# power.net
KiCad netlist of a schematic drawn in Altium Designer
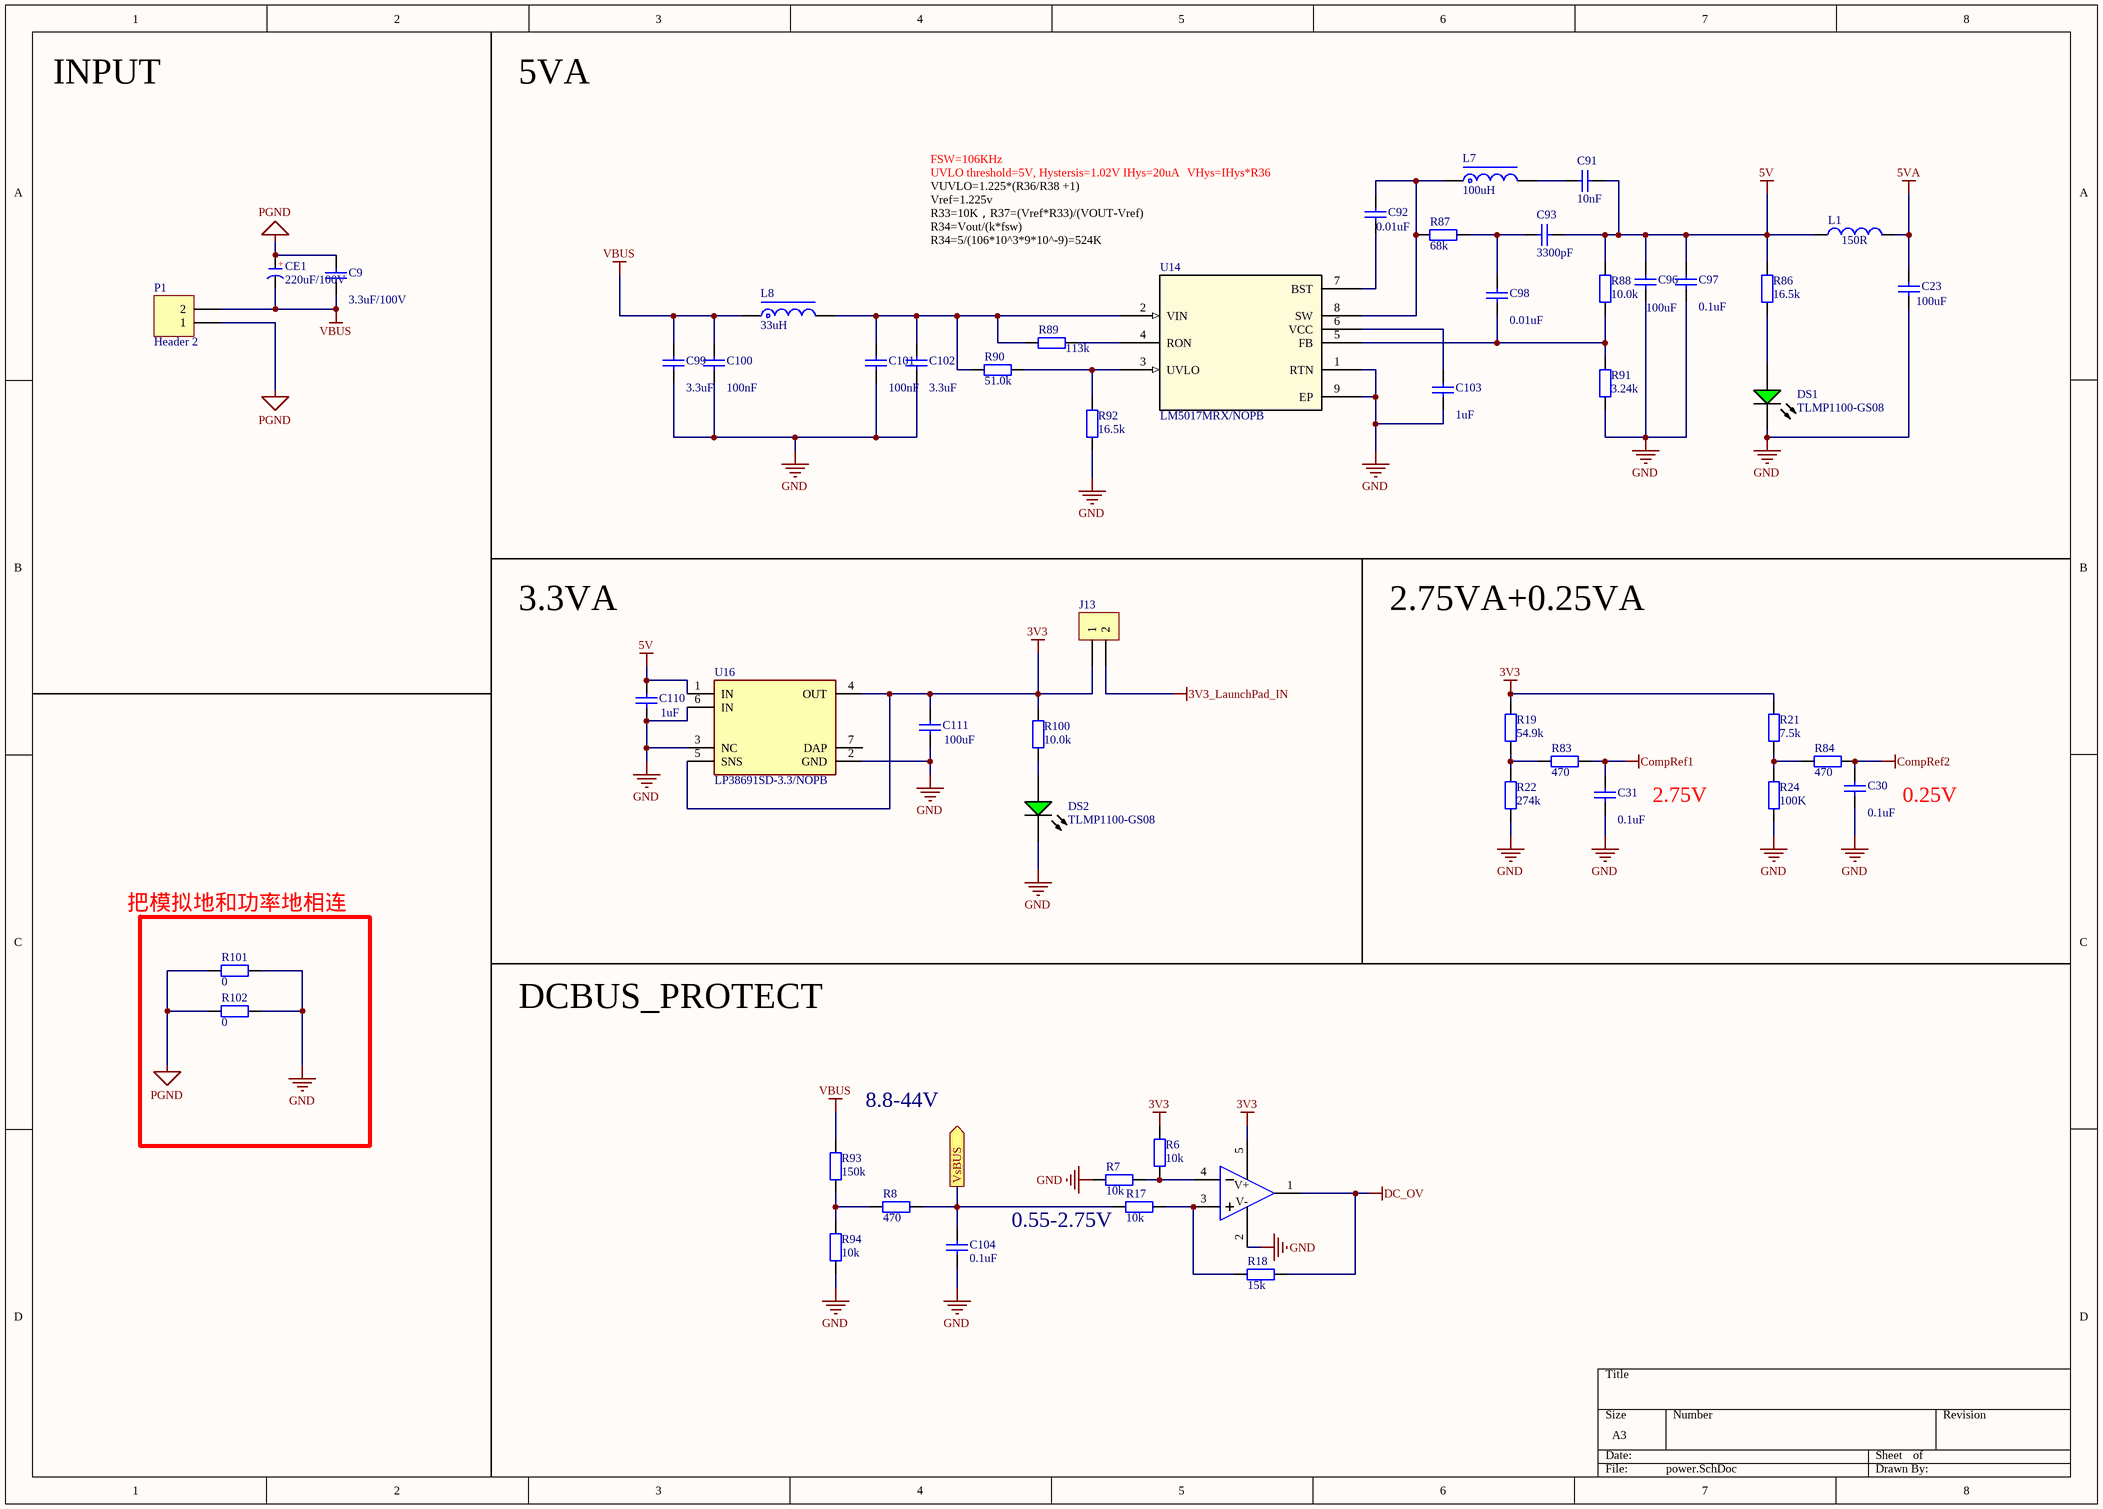
[diagram p0: power.SchDoc]

(export (version "E")
  (design (tool "Eeschema 10.0.6"))
  (components
    (comp (ref "C9")
      (value "3.3uF/100V")
      (footprint "CAPC1608X06N")
      (description "Capacitor")
      (fields (field (name "PUBLISHER") "Altium Limited"))
      (libsource (lib "Simscale") (part "Cap"))
    )
    (comp (ref "C23")
      (value "100uF")
      (footprint "CAPC1608X06N")
      (description "Capacitor")
      (fields (field (name "PUBLISHER") "Altium Limited"))
      (libsource (lib "Simscale") (part "Cap"))
    )
    (comp (ref "C30")
      (value "0.1uF")
      (footprint "CAPC1608X06N")
      (description "Capacitor")
      (fields (field (name "PUBLISHER") "Altium Limited"))
      (libsource (lib "Simscale") (part "Cap"))
    )
    (comp (ref "C31")
      (value "0.1uF")
      (footprint "CAPC1608X06N")
      (description "Capacitor")
      (fields (field (name "PUBLISHER") "Altium Limited"))
      (libsource (lib "Simscale") (part "Cap"))
    )
    (comp (ref "C91")
      (value "10nF")
      (footprint "CAPC1608X06N")
      (description "Capacitor")
      (fields (field (name "PUBLISHER") "Altium Limited"))
      (libsource (lib "Simscale") (part "Cap"))
    )
    (comp (ref "C92")
      (value "0.01uF")
      (footprint "CAPC1608X06N")
      (description "Capacitor")
      (fields (field (name "PUBLISHER") "Altium Limited"))
      (libsource (lib "Simscale") (part "Cap"))
    )
    (comp (ref "C93")
      (value "3300pF")
      (footprint "CAPC1608X06N")
      (description "Capacitor")
      (fields (field (name "PUBLISHER") "Altium Limited"))
      (libsource (lib "Simscale") (part "Cap"))
    )
    (comp (ref "C96")
      (value "100uF")
      (footprint "CAPC1608X06N")
      (description "Capacitor")
      (fields (field (name "PUBLISHER") "Altium Limited"))
      (libsource (lib "Simscale") (part "Cap"))
    )
    (comp (ref "C97")
      (value "0.1uF")
      (footprint "CAPC1608X06N")
      (description "Capacitor")
      (fields (field (name "PUBLISHER") "Altium Limited"))
      (libsource (lib "Simscale") (part "Cap"))
    )
    (comp (ref "C98")
      (value "0.01uF")
      (footprint "CAPC1608X06N")
      (description "Capacitor")
      (fields (field (name "PUBLISHER") "Altium Limited"))
      (libsource (lib "Simscale") (part "Cap"))
    )
    (comp (ref "C99")
      (value "3.3uF")
      (footprint "CAPC1608X06N")
      (description "Capacitor")
      (fields (field (name "PUBLISHER") "Altium Limited"))
      (libsource (lib "Soardra") (part "Cap"))
    )
    (comp (ref "C100")
      (value "100nF")
      (footprint "CAPC1608X06N")
      (description "Capacitor")
      (fields (field (name "PUBLISHER") "Altium Limited"))
      (libsource (lib "Soardra") (part "Cap"))
    )
    (comp (ref "C101")
      (value "100nF")
      (footprint "CAPC1608X06N")
      (description "Capacitor")
      (fields (field (name "PUBLISHER") "Altium Limited"))
      (libsource (lib "Simscale") (part "Cap"))
    )
    (comp (ref "C102")
      (value "3.3uF")
      (footprint "CAPC1608X06N")
      (description "Capacitor")
      (fields (field (name "PUBLISHER") "Altium Limited"))
      (libsource (lib "Simscale") (part "Cap"))
    )
    (comp (ref "C103")
      (value "1uF")
      (footprint "CAPC1608X06N")
      (description "Capacitor")
      (fields (field (name "PUBLISHER") "Altium Limited"))
      (libsource (lib "Simscale") (part "Cap"))
    )
    (comp (ref "C104")
      (value "0.1uF")
      (footprint "CAPC1608X06N")
      (description "Capacitor")
      (fields (field (name "PUBLISHER") "Altium Limited"))
      (libsource (lib "Simscale") (part "Cap"))
    )
    (comp (ref "C110")
      (value "1uF")
      (footprint "CAPC1608X06N")
      (description "Capacitor")
      (fields (field (name "PUBLISHER") "Altium Limited"))
      (libsource (lib "Simscale") (part "Cap"))
    )
    (comp (ref "C111")
      (value "100uF")
      (footprint "CAPC1608X06N")
      (description "Capacitor")
      (fields (field (name "PUBLISHER") "Altium Limited"))
      (libsource (lib "Simscale") (part "Cap"))
    )
    (comp (ref "CE1")
      (value "220uF/100V")
      (footprint "CAP 5.0*12.5*20")
      (description "直插电解电容")
      (libsource (lib "0.1 - 电阻-电容-电感") (part "CE"))
    )
    (comp (ref "DS1")
      (value "TLMP1100-GS08")
      (footprint "VISH-TLMX1100_V")
      (description "LED, RED, 2.1 V, -40 to 100 degC, 2-Pin SMD (0603), RoHS, Tape and Reel")
      (fields (field (name "TOLERANCE") "5%"))
      (libsource (lib "Simscale") (part "CMP-1666-00027-1_1"))
    )
    (comp (ref "DS2")
      (value "TLMP1100-GS08")
      (footprint "VISH-TLMX1100_V")
      (description "LED, RED, 2.1 V, -40 to 100 degC, 2-Pin SMD (0603), RoHS, Tape and Reel")
      (fields (field (name "TOLERANCE") "5%"))
      (libsource (lib "Simscale") (part "CMP-1666-00027-1_1"))
    )
    (comp (ref "J13") (value "CON2") (footprint "DG1282-5.0") (libsource (lib "常用元件库") (part "CON2")))
    (comp (ref "L1")
      (value "150R")
      (footprint "IND-SMD_L5.5-W5.2")
      (description "Inductor")
      (fields (field (name "PUBLISHER") "Altium Limited"))
      (libsource (lib "Miscellaneous Devices") (part "Inductor"))
    )
    (comp (ref "L7")
      (value "100uH")
      (footprint "NR4018")
      (description "NR磁胶电感")
      (fields (field (name "版权归属") "来自淘宝 ID：黄晶宝石"))
      (libsource (lib "0.1 - 电阻-电容-电感") (part "L-NR"))
    )
    (comp (ref "L8")
      (value "33uH")
      (footprint "NR2520")
      (description "NR磁胶电感")
      (fields (field (name "版权归属") "来自淘宝 ID：黄晶宝石"))
      (libsource (lib "0.1 - 电阻-电容-电感") (part "L-NR"))
    )
    (comp (ref "P1")
      (value "Header 2")
      (footprint "HDR1X2")
      (description "Header, 2-Pin")
      (fields (field (name "PUBLISHER") "Altium Limited"))
      (libsource (lib "Simscale") (part "Header 2"))
    )
    (comp (ref "R6")
      (value "10k")
      (footprint "RESC1608X05N")
      (description "贴片电阻")
      (libsource (lib "") (part "0603 100KΩ (1003) 1%_4_3"))
    )
    (comp (ref "R7")
      (value "10k")
      (footprint "RESC1608X05N")
      (description "贴片电阻")
      (libsource (lib "") (part "0603 100KΩ (1003) 1%_4_2"))
    )
    (comp (ref "R8")
      (value "470")
      (footprint "RESC1608X05N")
      (description "贴片电阻")
      (libsource (lib "") (part "0603 100KΩ (1003) 1%_4_2"))
    )
    (comp (ref "R17")
      (value "10k")
      (footprint "RESC1608X05N")
      (description "贴片电阻")
      (libsource (lib "") (part "0603 100KΩ (1003) 1%_4_2"))
    )
    (comp (ref "R18")
      (value "15k")
      (footprint "RESC1608X05N")
      (description "贴片电阻")
      (libsource (lib "") (part "0603 100KΩ (1003) 1%_4_2"))
    )
    (comp (ref "R19")
      (value "54.9k")
      (footprint "RESC1608X05N")
      (description "贴片电阻")
      (libsource (lib "Simscale") (part "0603 100KΩ (1003) 1%_4"))
    )
    (comp (ref "R21")
      (value "7.5k")
      (footprint "RESC1608X05N")
      (description "贴片电阻")
      (libsource (lib "Simscale") (part "0603 100KΩ (1003) 1%_4"))
    )
    (comp (ref "R22")
      (value "274k")
      (footprint "RESC1608X05N")
      (description "贴片电阻")
      (libsource (lib "Simscale") (part "0603 100KΩ (1003) 1%_4"))
    )
    (comp (ref "R24")
      (value "100K")
      (footprint "RESC1608X05N")
      (description "贴片电阻")
      (libsource (lib "Simscale") (part "0603 100KΩ (1003) 1%_4"))
    )
    (comp (ref "R83")
      (value "470")
      (footprint "RESC1608X05N")
      (description "贴片电阻")
      (libsource (lib "") (part "0603 100KΩ (1003) 1%_4_2"))
    )
    (comp (ref "R84")
      (value "470")
      (footprint "RESC1608X05N")
      (description "贴片电阻")
      (libsource (lib "") (part "0603 100KΩ (1003) 1%_4_2"))
    )
    (comp (ref "R86")
      (value "16.5k")
      (footprint "RESC1608X05N")
      (description "贴片电阻")
      (libsource (lib "Simscale") (part "0603 100KΩ (1003) 1%_4"))
    )
    (comp (ref "R87")
      (value "68k")
      (footprint "RESC1608X05N")
      (description "贴片电阻")
      (libsource (lib "") (part "0603 100KΩ (1003) 1%_4_2"))
    )
    (comp (ref "R88")
      (value "10.0k")
      (footprint "RESC1608X05N")
      (description "贴片电阻")
      (libsource (lib "Simscale") (part "0603 100KΩ (1003) 1%_4"))
    )
    (comp (ref "R89")
      (value "113k")
      (footprint "RESC1608X05N")
      (description "贴片电阻")
      (libsource (lib "") (part "0603 100KΩ (1003) 1%_4_1"))
    )
    (comp (ref "R90")
      (value "51.0k")
      (footprint "RESC1608X05N")
      (description "贴片电阻")
      (libsource (lib "") (part "0603 100KΩ (1003) 1%_4_1"))
    )
    (comp (ref "R91")
      (value "3.24k")
      (footprint "RESC1608X05N")
      (description "贴片电阻")
      (libsource (lib "Simscale") (part "0603 100KΩ (1003) 1%_4"))
    )
    (comp (ref "R92")
      (value "16.5k")
      (footprint "RESC1608X05N")
      (description "贴片电阻")
      (libsource (lib "Simscale") (part "0603 100KΩ (1003) 1%_4"))
    )
    (comp (ref "R93")
      (value "150k")
      (footprint "RESC1608X05N")
      (description "贴片电阻")
      (libsource (lib "Simscale") (part "0603 100KΩ (1003) 1%_4"))
    )
    (comp (ref "R94")
      (value "10k")
      (footprint "RESC1608X05N")
      (description "贴片电阻")
      (libsource (lib "Simscale") (part "0603 100KΩ (1003) 1%_4"))
    )
    (comp (ref "R100")
      (value "10.0k")
      (footprint "RESC1608X05N")
      (description "贴片电阻")
      (libsource (lib "Simscale") (part "0603 100KΩ (1003) 1%_4"))
    )
    (comp (ref "R101")
      (value "0")
      (footprint "RESC1608X05N")
      (description "贴片电阻")
      (libsource (lib "") (part "0603 100KΩ (1003) 1%_4_2"))
    )
    (comp (ref "R102")
      (value "0")
      (footprint "RESC1608X05N")
      (description "贴片电阻")
      (libsource (lib "") (part "0603 100KΩ (1003) 1%_4_2"))
    )
    (comp (ref "U6")
      (value "TLV3201AIDBVR")
      (footprint "SOT-23-5_L3.0-W1.7-P0.95-LS2.8-BR")
      (fields (field (name "MANUFACTURER") "TI(德州仪器)"))
      (libsource (lib "TLV3201AIDBVR1_TLV3201AIDBVR.schdoc") (part "TLV3201AIDBVR"))
    )
    (comp (ref "U14")
      (value "LM5017MRX/NOPB")
      (footprint "DDA8_3P1X2P41")
      (description "No Description Available")
      (fields (field (name "COPYRIGHT") "Copyright (C) 2024 Ultra Librarian. All rights reserved."))
      (libsource (lib "LM5017MRXNOPB") (part "LM5017MRXNOPB"))
    )
    (comp (ref "U16")
      (value "LP38691SD-3.3/NOPB")
      (footprint "FP-NGG0006A-MFG")
      (description "IC REG LINEAR 3.3V 500MA 6WSON")
      (libsource (lib "Altium Content Vault") (part "560842684473682ac15f67370b5a5a6"))
    )
  )
  (nets
    (net (code "1") (name "/VsBUS") (class "Default")
      (node (ref "C104") (pin "1") (pinfunction "1_1") (pintype "passive"))
      (node (ref "R17") (pin "2") (pinfunction "2_2") (pintype "passive"))
      (node (ref "R8") (pin "1") (pinfunction "1_1") (pintype "passive"))
    )
    (net (code "2") (name "3V3") (class "Default")
      (node (ref "C111") (pin "2") (pinfunction "2_2") (pintype "passive"))
      (node (ref "J13") (pin "1") (pinfunction "1_1") (pintype "passive"))
      (node (ref "R100") (pin "2") (pinfunction "2_2") (pintype "passive"))
      (node (ref "R19") (pin "2") (pinfunction "2_2") (pintype "passive"))
      (node (ref "R21") (pin "2") (pinfunction "2_2") (pintype "passive"))
      (node (ref "R6") (pin "1") (pinfunction "1_1") (pintype "passive"))
      (node (ref "U16") (pin "4") (pinfunction "OUT_4") (pintype "power_in"))
      (node (ref "U16") (pin "5") (pinfunction "SNS_5") (pintype "power_in"))
      (node (ref "U6") (pin "5") (pinfunction "VCC_5") (pintype "passive"))
    )
    (net (code "3") (name "3V3_LaunchPad_IN") (class "Default")
      (node (ref "J13") (pin "2") (pinfunction "2_2") (pintype "passive"))
    )
    (net (code "4") (name "5V") (class "Default")
      (node (ref "C110") (pin "2") (pinfunction "2_2") (pintype "passive"))
      (node (ref "C91") (pin "2") (pinfunction "2_2") (pintype "passive"))
      (node (ref "C93") (pin "1") (pinfunction "1_1") (pintype "passive"))
      (node (ref "C96") (pin "2") (pinfunction "2_2") (pintype "passive"))
      (node (ref "C97") (pin "2") (pinfunction "2_2") (pintype "passive"))
      (node (ref "L1") (pin "1") (pinfunction "1_1") (pintype "passive"))
      (node (ref "R86") (pin "2") (pinfunction "2_2") (pintype "passive"))
      (node (ref "R88") (pin "2") (pinfunction "2_2") (pintype "passive"))
      (node (ref "U16") (pin "1") (pinfunction "IN_1") (pintype "power_in"))
    )
    (net (code "5") (name "5VA") (class "Default")
      (node (ref "C23") (pin "2") (pinfunction "2_2") (pintype "passive"))
      (node (ref "L1") (pin "2") (pinfunction "2_2") (pintype "passive"))
    )
    (net (code "6") (name "CompRef1") (class "Default")
      (node (ref "C31") (pin "2") (pinfunction "2_2") (pintype "passive"))
      (node (ref "R83") (pin "1") (pinfunction "1_1") (pintype "passive"))
    )
    (net (code "7") (name "CompRef2") (class "Default")
      (node (ref "C30") (pin "2") (pinfunction "2_2") (pintype "passive"))
      (node (ref "R84") (pin "1") (pinfunction "1_1") (pintype "passive"))
    )
    (net (code "8") (name "DC_OV") (class "Default")
      (node (ref "R18") (pin "1") (pinfunction "1_1") (pintype "passive"))
      (node (ref "U6") (pin "1") (pinfunction "OUT_1") (pintype "passive"))
    )
    (net (code "9") (name "GND") (class "Default")
      (node (ref "C100") (pin "2") (pinfunction "2_2") (pintype "passive"))
      (node (ref "C101") (pin "2") (pinfunction "2_2") (pintype "passive"))
      (node (ref "C102") (pin "1") (pinfunction "1_1") (pintype "passive"))
      (node (ref "C103") (pin "1") (pinfunction "1_1") (pintype "passive"))
      (node (ref "C104") (pin "2") (pinfunction "2_2") (pintype "passive"))
      (node (ref "C110") (pin "1") (pinfunction "1_1") (pintype "passive"))
      (node (ref "C111") (pin "1") (pinfunction "1_1") (pintype "passive"))
      (node (ref "C23") (pin "1") (pinfunction "1_1") (pintype "passive"))
      (node (ref "C30") (pin "1") (pinfunction "1_1") (pintype "passive"))
      (node (ref "C31") (pin "1") (pinfunction "1_1") (pintype "passive"))
      (node (ref "C96") (pin "1") (pinfunction "1_1") (pintype "passive"))
      (node (ref "C97") (pin "1") (pinfunction "1_1") (pintype "passive"))
      (node (ref "C99") (pin "2") (pinfunction "2_2") (pintype "passive"))
      (node (ref "DS1") (pin "2") (pinfunction "K_2") (pintype "passive"))
      (node (ref "DS2") (pin "2") (pinfunction "K_2") (pintype "passive"))
      (node (ref "R101") (pin "1") (pinfunction "1_1") (pintype "passive"))
      (node (ref "R102") (pin "1") (pinfunction "1_1") (pintype "passive"))
      (node (ref "R22") (pin "1") (pinfunction "1_1") (pintype "passive"))
      (node (ref "R24") (pin "1") (pinfunction "1_1") (pintype "passive"))
      (node (ref "R7") (pin "2") (pinfunction "2_2") (pintype "passive"))
      (node (ref "R91") (pin "1") (pinfunction "1_1") (pintype "passive"))
      (node (ref "R92") (pin "1") (pinfunction "1_1") (pintype "passive"))
      (node (ref "R94") (pin "1") (pinfunction "1_1") (pintype "passive"))
      (node (ref "U14") (pin "1") (pinfunction "RTN_1") (pintype "power_in"))
      (node (ref "U14") (pin "9") (pinfunction "EP_9") (pintype "passive"))
      (node (ref "U16") (pin "2") (pinfunction "GND_2") (pintype "power_in"))
      (node (ref "U16") (pin "3") (pinfunction "NC_3") (pintype "passive"))
      (node (ref "U16") (pin "6") (pinfunction "IN_6") (pintype "power_in"))
      (node (ref "U6") (pin "2") (pinfunction "GND_2") (pintype "passive"))
    )
    (net (code "10") (name "Net-(C91-Pad1)") (class "Default")
      (node (ref "C91") (pin "1") (pinfunction "1_1") (pintype "passive"))
      (node (ref "L7") (pin "2") (pinfunction "2_2") (pintype "passive"))
    )
    (net (code "11") (name "Net-(C93-Pad2)") (class "Default")
      (node (ref "C93") (pin "2") (pinfunction "2_2") (pintype "passive"))
      (node (ref "C98") (pin "2") (pinfunction "2_2") (pintype "passive"))
      (node (ref "R87") (pin "1") (pinfunction "1_1") (pintype "passive"))
    )
    (net (code "12") (name "Net-(DS1-A)") (class "Default")
      (node (ref "DS1") (pin "1") (pinfunction "A_1") (pintype "passive"))
      (node (ref "R86") (pin "1") (pinfunction "1_1") (pintype "passive"))
    )
    (net (code "13") (name "Net-(DS2-A)") (class "Default")
      (node (ref "DS2") (pin "1") (pinfunction "A_1") (pintype "passive"))
      (node (ref "R100") (pin "1") (pinfunction "1_1") (pintype "passive"))
    )
    (net (code "14") (name "Net-(R8-Pad2)") (class "Default")
      (node (ref "R8") (pin "2") (pinfunction "2_2") (pintype "passive"))
      (node (ref "R93") (pin "1") (pinfunction "1_1") (pintype "passive"))
      (node (ref "R94") (pin "2") (pinfunction "2_2") (pintype "passive"))
    )
    (net (code "15") (name "Net-(R19-Pad1)") (class "Default")
      (node (ref "R19") (pin "1") (pinfunction "1_1") (pintype "passive"))
      (node (ref "R22") (pin "2") (pinfunction "2_2") (pintype "passive"))
      (node (ref "R83") (pin "2") (pinfunction "2_2") (pintype "passive"))
    )
    (net (code "16") (name "Net-(R21-Pad1)") (class "Default")
      (node (ref "R21") (pin "1") (pinfunction "1_1") (pintype "passive"))
      (node (ref "R24") (pin "2") (pinfunction "2_2") (pintype "passive"))
      (node (ref "R84") (pin "2") (pinfunction "2_2") (pintype "passive"))
    )
    (net (code "17") (name "Net-(U6-IN+)") (class "Default")
      (node (ref "R17") (pin "1") (pinfunction "1_1") (pintype "passive"))
      (node (ref "R18") (pin "2") (pinfunction "2_2") (pintype "passive"))
      (node (ref "U6") (pin "3") (pinfunction "IN+_3") (pintype "passive"))
    )
    (net (code "18") (name "Net-(U6-IN-)") (class "Default")
      (node (ref "R6") (pin "2") (pinfunction "2_2") (pintype "passive"))
      (node (ref "R7") (pin "1") (pinfunction "1_1") (pintype "passive"))
      (node (ref "U6") (pin "4") (pinfunction "IN-_4") (pintype "passive"))
    )
    (net (code "19") (name "Net-(U14-BST)") (class "Default")
      (node (ref "C92") (pin "1") (pinfunction "1_1") (pintype "passive"))
      (node (ref "U14") (pin "7") (pinfunction "BST_7") (pintype "passive"))
    )
    (net (code "20") (name "Net-(U14-FB)") (class "Default")
      (node (ref "C98") (pin "1") (pinfunction "1_1") (pintype "passive"))
      (node (ref "R88") (pin "1") (pinfunction "1_1") (pintype "passive"))
      (node (ref "R91") (pin "2") (pinfunction "2_2") (pintype "passive"))
      (node (ref "U14") (pin "5") (pinfunction "FB_5") (pintype "passive"))
    )
    (net (code "21") (name "Net-(U14-RON)") (class "Default")
      (node (ref "R89") (pin "2") (pinfunction "2_2") (pintype "passive"))
      (node (ref "U14") (pin "4") (pinfunction "RON_4") (pintype "passive"))
    )
    (net (code "22") (name "Net-(U14-SW)") (class "Default")
      (node (ref "C92") (pin "2") (pinfunction "2_2") (pintype "passive"))
      (node (ref "L7") (pin "1") (pinfunction "1_1") (pintype "passive"))
      (node (ref "R87") (pin "2") (pinfunction "2_2") (pintype "passive"))
      (node (ref "U14") (pin "8") (pinfunction "SW_8") (pintype "passive"))
    )
    (net (code "23") (name "Net-(U14-UVLO)") (class "Default")
      (node (ref "R90") (pin "2") (pinfunction "2_2") (pintype "passive"))
      (node (ref "R92") (pin "2") (pinfunction "2_2") (pintype "passive"))
      (node (ref "U14") (pin "3") (pinfunction "UVLO_3") (pintype "input"))
    )
    (net (code "24") (name "Net-(U14-VCC)") (class "Default")
      (node (ref "C103") (pin "2") (pinfunction "2_2") (pintype "passive"))
      (node (ref "U14") (pin "6") (pinfunction "VCC_6") (pintype "power_in"))
    )
    (net (code "25") (name "Net-(U14-VIN)") (class "Default")
      (node (ref "C101") (pin "1") (pinfunction "1_1") (pintype "passive"))
      (node (ref "C102") (pin "2") (pinfunction "2_2") (pintype "passive"))
      (node (ref "L8") (pin "2") (pinfunction "2_2") (pintype "passive"))
      (node (ref "R89") (pin "1") (pinfunction "1_1") (pintype "passive"))
      (node (ref "R90") (pin "1") (pinfunction "1_1") (pintype "passive"))
      (node (ref "U14") (pin "2") (pinfunction "VIN_2") (pintype "input"))
    )
    (net (code "26") (name "PGND") (class "Default")
      (node (ref "C9") (pin "2") (pinfunction "2_2") (pintype "passive"))
      (node (ref "CE1") (pin "1") (pinfunction "A_1") (pintype "passive"))
      (node (ref "P1") (pin "1") (pinfunction "1_1") (pintype "passive"))
      (node (ref "R101") (pin "2") (pinfunction "2_2") (pintype "passive"))
      (node (ref "R102") (pin "2") (pinfunction "2_2") (pintype "passive"))
    )
    (net (code "27") (name "VBUS") (class "Default")
      (node (ref "C100") (pin "1") (pinfunction "1_1") (pintype "passive"))
      (node (ref "C9") (pin "1") (pinfunction "1_1") (pintype "passive"))
      (node (ref "C99") (pin "1") (pinfunction "1_1") (pintype "passive"))
      (node (ref "CE1") (pin "2") (pinfunction "K_2") (pintype "passive"))
      (node (ref "L8") (pin "1") (pinfunction "1_1") (pintype "passive"))
      (node (ref "P1") (pin "2") (pinfunction "2_2") (pintype "passive"))
      (node (ref "R93") (pin "2") (pinfunction "2_2") (pintype "passive"))
    )
    (net (code "28") (name "unconnected-(U16-DAP-Pad7)") (class "Default")
      (node (ref "U16") (pin "7") (pinfunction "DAP_7") (pintype "power_in"))
    )
  )
)
